# binw2.net
KiCad netlist of a schematic drawn in EAGLE
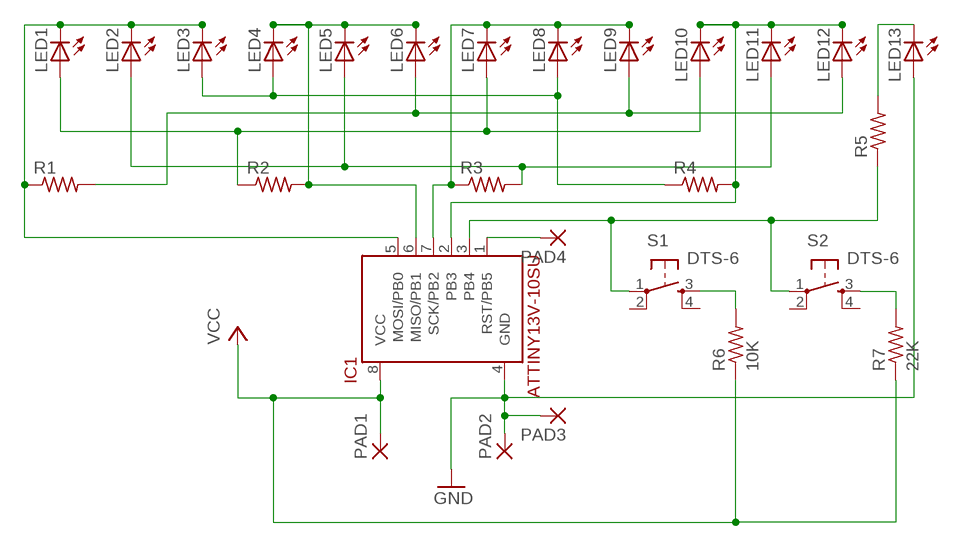
[diagram p0: schematic, sheet 1]

(export (version "E")
  (design (tool "Eeschema 10.0.6"))
  (components
    (comp (ref "IC1")
      (value "ATTINY13V-10SU")
      (footprint "eagle-import:SOIC8")
      (libsource (lib "eagle-import") (part "ATTINY13V-10SU"))
    )
    (comp (ref "LED1")
      (value "LEDCHIP-LED0805")
      (footprint "eagle-import:CHIP-LED0805")
      (libsource (lib "eagle-import") (part "LEDCHIP-LED0805"))
    )
    (comp (ref "LED2")
      (value "LEDCHIP-LED0805")
      (footprint "eagle-import:CHIP-LED0805")
      (libsource (lib "eagle-import") (part "LEDCHIP-LED0805"))
    )
    (comp (ref "LED3")
      (value "LEDCHIP-LED0805")
      (footprint "eagle-import:CHIP-LED0805")
      (libsource (lib "eagle-import") (part "LEDCHIP-LED0805"))
    )
    (comp (ref "LED4")
      (value "LEDCHIP-LED0805")
      (footprint "eagle-import:CHIP-LED0805")
      (libsource (lib "eagle-import") (part "LEDCHIP-LED0805"))
    )
    (comp (ref "LED5")
      (value "LEDCHIP-LED0805")
      (footprint "eagle-import:CHIP-LED0805")
      (libsource (lib "eagle-import") (part "LEDCHIP-LED0805"))
    )
    (comp (ref "LED6")
      (value "LEDCHIP-LED0805")
      (footprint "eagle-import:CHIP-LED0805")
      (libsource (lib "eagle-import") (part "LEDCHIP-LED0805"))
    )
    (comp (ref "LED7")
      (value "LEDCHIP-LED0805")
      (footprint "eagle-import:CHIP-LED0805")
      (libsource (lib "eagle-import") (part "LEDCHIP-LED0805"))
    )
    (comp (ref "LED8")
      (value "LEDCHIP-LED0805")
      (footprint "eagle-import:CHIP-LED0805")
      (libsource (lib "eagle-import") (part "LEDCHIP-LED0805"))
    )
    (comp (ref "LED9")
      (value "LEDCHIP-LED0805")
      (footprint "eagle-import:CHIP-LED0805")
      (libsource (lib "eagle-import") (part "LEDCHIP-LED0805"))
    )
    (comp (ref "LED10")
      (value "LEDCHIP-LED0805")
      (footprint "eagle-import:CHIP-LED0805")
      (libsource (lib "eagle-import") (part "LEDCHIP-LED0805"))
    )
    (comp (ref "LED11")
      (value "LEDCHIP-LED0805")
      (footprint "eagle-import:CHIP-LED0805")
      (libsource (lib "eagle-import") (part "LEDCHIP-LED0805"))
    )
    (comp (ref "LED12")
      (value "LEDCHIP-LED0805")
      (footprint "eagle-import:CHIP-LED0805")
      (libsource (lib "eagle-import") (part "LEDCHIP-LED0805"))
    )
    (comp (ref "LED13")
      (value "LEDCHIP-LED0805")
      (footprint "eagle-import:CHIP-LED0805")
      (libsource (lib "eagle-import") (part "LEDCHIP-LED0805"))
    )
    (comp (ref "PAD1")
      (value "1,6/0,8")
      (footprint "eagle-import:1,6_0,8")
      (libsource (lib "eagle-import") (part "1,6/0,8"))
    )
    (comp (ref "PAD2")
      (value "1,6/0,8")
      (footprint "eagle-import:1,6_0,8")
      (libsource (lib "eagle-import") (part "1,6/0,8"))
    )
    (comp (ref "PAD3")
      (value "1,6/0,8")
      (footprint "eagle-import:1,6_0,8")
      (libsource (lib "eagle-import") (part "1,6/0,8"))
    )
    (comp (ref "PAD4")
      (value "1,6/0,8")
      (footprint "eagle-import:1,6_0,8")
      (libsource (lib "eagle-import") (part "1,6/0,8"))
    )
    (comp (ref "R1")
      (value "R-US_R0805")
      (footprint "eagle-import:R0805")
      (libsource (lib "eagle-import") (part "R-US_R0805"))
    )
    (comp (ref "R2")
      (value "R-US_R0805")
      (footprint "eagle-import:R0805")
      (libsource (lib "eagle-import") (part "R-US_R0805"))
    )
    (comp (ref "R3")
      (value "R-US_R0805")
      (footprint "eagle-import:R0805")
      (libsource (lib "eagle-import") (part "R-US_R0805"))
    )
    (comp (ref "R4")
      (value "R-US_R0805")
      (footprint "eagle-import:R0805")
      (libsource (lib "eagle-import") (part "R-US_R0805"))
    )
    (comp (ref "R5")
      (value "R-US_R0805")
      (footprint "eagle-import:R0805")
      (libsource (lib "eagle-import") (part "R-US_R0805"))
    )
    (comp (ref "R6")
      (value "10K")
      (footprint "eagle-import:R0805")
      (libsource (lib "eagle-import") (part "R-US_R0805"))
    )
    (comp (ref "R7")
      (value "22K")
      (footprint "eagle-import:R0805")
      (libsource (lib "eagle-import") (part "R-US_R0805"))
    )
    (comp (ref "S1")
      (value "DTS-6")
      (footprint "eagle-import:DTS-6")
      (libsource (lib "eagle-import") (part "DTS-6"))
    )
    (comp (ref "S2")
      (value "DTS-6")
      (footprint "eagle-import:DTS-6")
      (libsource (lib "eagle-import") (part "DTS-6"))
    )
  )
  (nets
    (net (code "1") (name "GND") (class "Default")
      (node (ref "IC1") (pin "4") (pinfunction "GND_4") (pintype "power_in"))
      (node (ref "LED13") (pin "A") (pinfunction "A_A") (pintype "passive"))
      (node (ref "PAD2") (pin "1") (pinfunction "P_1") (pintype "passive"))
      (node (ref "PAD3") (pin "1") (pinfunction "P_1") (pintype "passive"))
    )
    (net (code "2") (name "Net-(IC1-MISO{slash}PB1)") (class "Default")
      (node (ref "IC1") (pin "6") (pinfunction "MISO/PB1_6") (pintype "bidirectional"))
      (node (ref "LED4") (pin "C") (pinfunction "C_C") (pintype "passive"))
      (node (ref "LED5") (pin "C") (pinfunction "C_C") (pintype "passive"))
      (node (ref "LED6") (pin "C") (pinfunction "C_C") (pintype "passive"))
      (node (ref "R2") (pin "2") (pinfunction "2_2") (pintype "passive"))
    )
    (net (code "3") (name "Net-(IC1-MOSI{slash}PB0)") (class "Default")
      (node (ref "IC1") (pin "5") (pinfunction "MOSI/PB0_5") (pintype "bidirectional"))
      (node (ref "LED1") (pin "C") (pinfunction "C_C") (pintype "passive"))
      (node (ref "LED2") (pin "C") (pinfunction "C_C") (pintype "passive"))
      (node (ref "LED3") (pin "C") (pinfunction "C_C") (pintype "passive"))
      (node (ref "R1") (pin "1") (pinfunction "1_1") (pintype "passive"))
    )
    (net (code "4") (name "Net-(IC1-PB3)") (class "Default")
      (node (ref "IC1") (pin "2") (pinfunction "PB3_2") (pintype "bidirectional"))
      (node (ref "LED10") (pin "C") (pinfunction "C_C") (pintype "passive"))
      (node (ref "LED11") (pin "C") (pinfunction "C_C") (pintype "passive"))
      (node (ref "LED12") (pin "C") (pinfunction "C_C") (pintype "passive"))
      (node (ref "R4") (pin "2") (pinfunction "2_2") (pintype "passive"))
    )
    (net (code "5") (name "Net-(IC1-PB4)") (class "Default")
      (node (ref "IC1") (pin "3") (pinfunction "PB4_3") (pintype "bidirectional"))
      (node (ref "R5") (pin "1") (pinfunction "1_1") (pintype "passive"))
      (node (ref "S1") (pin "1") (pinfunction "1_1") (pintype "passive"))
      (node (ref "S2") (pin "1") (pinfunction "1_1") (pintype "passive"))
    )
    (net (code "6") (name "Net-(IC1-RST{slash}PB5)") (class "Default")
      (node (ref "IC1") (pin "1") (pinfunction "RST/PB5_1") (pintype "bidirectional"))
      (node (ref "PAD4") (pin "1") (pinfunction "P_1") (pintype "passive"))
    )
    (net (code "7") (name "Net-(IC1-SCK{slash}PB2)") (class "Default")
      (node (ref "IC1") (pin "7") (pinfunction "SCK/PB2_7") (pintype "bidirectional"))
      (node (ref "LED7") (pin "C") (pinfunction "C_C") (pintype "passive"))
      (node (ref "LED8") (pin "C") (pinfunction "C_C") (pintype "passive"))
      (node (ref "LED9") (pin "C") (pinfunction "C_C") (pintype "passive"))
      (node (ref "R3") (pin "1") (pinfunction "1_1") (pintype "passive"))
    )
    (net (code "8") (name "Net-(LED1-PadA)") (class "Default")
      (node (ref "LED1") (pin "A") (pinfunction "A_A") (pintype "passive"))
      (node (ref "LED10") (pin "A") (pinfunction "A_A") (pintype "passive"))
      (node (ref "LED7") (pin "A") (pinfunction "A_A") (pintype "passive"))
      (node (ref "R2") (pin "1") (pinfunction "1_1") (pintype "passive"))
    )
    (net (code "9") (name "Net-(LED3-PadA)") (class "Default")
      (node (ref "LED3") (pin "A") (pinfunction "A_A") (pintype "passive"))
      (node (ref "LED4") (pin "A") (pinfunction "A_A") (pintype "passive"))
      (node (ref "LED8") (pin "A") (pinfunction "A_A") (pintype "passive"))
      (node (ref "R4") (pin "1") (pinfunction "1_1") (pintype "passive"))
    )
    (net (code "10") (name "Net-(LED11-PadA)") (class "Default")
      (node (ref "LED11") (pin "A") (pinfunction "A_A") (pintype "passive"))
      (node (ref "LED2") (pin "A") (pinfunction "A_A") (pintype "passive"))
      (node (ref "LED5") (pin "A") (pinfunction "A_A") (pintype "passive"))
      (node (ref "R3") (pin "2") (pinfunction "2_2") (pintype "passive"))
    )
    (net (code "11") (name "Net-(LED12-PadA)") (class "Default")
      (node (ref "LED12") (pin "A") (pinfunction "A_A") (pintype "passive"))
      (node (ref "LED6") (pin "A") (pinfunction "A_A") (pintype "passive"))
      (node (ref "LED9") (pin "A") (pinfunction "A_A") (pintype "passive"))
      (node (ref "R1") (pin "2") (pinfunction "2_2") (pintype "passive"))
    )
    (net (code "12") (name "Net-(LED13-PadC)") (class "Default")
      (node (ref "LED13") (pin "C") (pinfunction "C_C") (pintype "passive"))
      (node (ref "R5") (pin "2") (pinfunction "2_2") (pintype "passive"))
    )
    (net (code "13") (name "Net-(R6-Pad2)") (class "Default")
      (node (ref "R6") (pin "2") (pinfunction "2_2") (pintype "passive"))
      (node (ref "S1") (pin "3") (pinfunction "3_3") (pintype "passive"))
    )
    (net (code "14") (name "Net-(R7-Pad2)") (class "Default")
      (node (ref "R7") (pin "2") (pinfunction "2_2") (pintype "passive"))
      (node (ref "S2") (pin "3") (pinfunction "3_3") (pintype "passive"))
    )
    (net (code "15") (name "VCC") (class "Default")
      (node (ref "IC1") (pin "8") (pinfunction "VCC_8") (pintype "power_in"))
      (node (ref "PAD1") (pin "1") (pinfunction "P_1") (pintype "passive"))
      (node (ref "R6") (pin "1") (pinfunction "1_1") (pintype "passive"))
      (node (ref "R7") (pin "1") (pinfunction "1_1") (pintype "passive"))
    )
    (net (code "16") (name "unconnected-(S1-Pad2)") (class "Default")
      (node (ref "S1") (pin "2") (pinfunction "2_2") (pintype "passive"))
    )
    (net (code "17") (name "unconnected-(S1-Pad4)") (class "Default")
      (node (ref "S1") (pin "4") (pinfunction "4_4") (pintype "passive"))
    )
    (net (code "18") (name "unconnected-(S2-Pad2)") (class "Default")
      (node (ref "S2") (pin "2") (pinfunction "2_2") (pintype "passive"))
    )
    (net (code "19") (name "unconnected-(S2-Pad4)") (class "Default")
      (node (ref "S2") (pin "4") (pinfunction "4_4") (pintype "passive"))
    )
  )
)
